# LCDTFT_FPC40P_SPI3_3p2INCH_RTP.net
KiCad netlist of a schematic drawn in Altium Designer
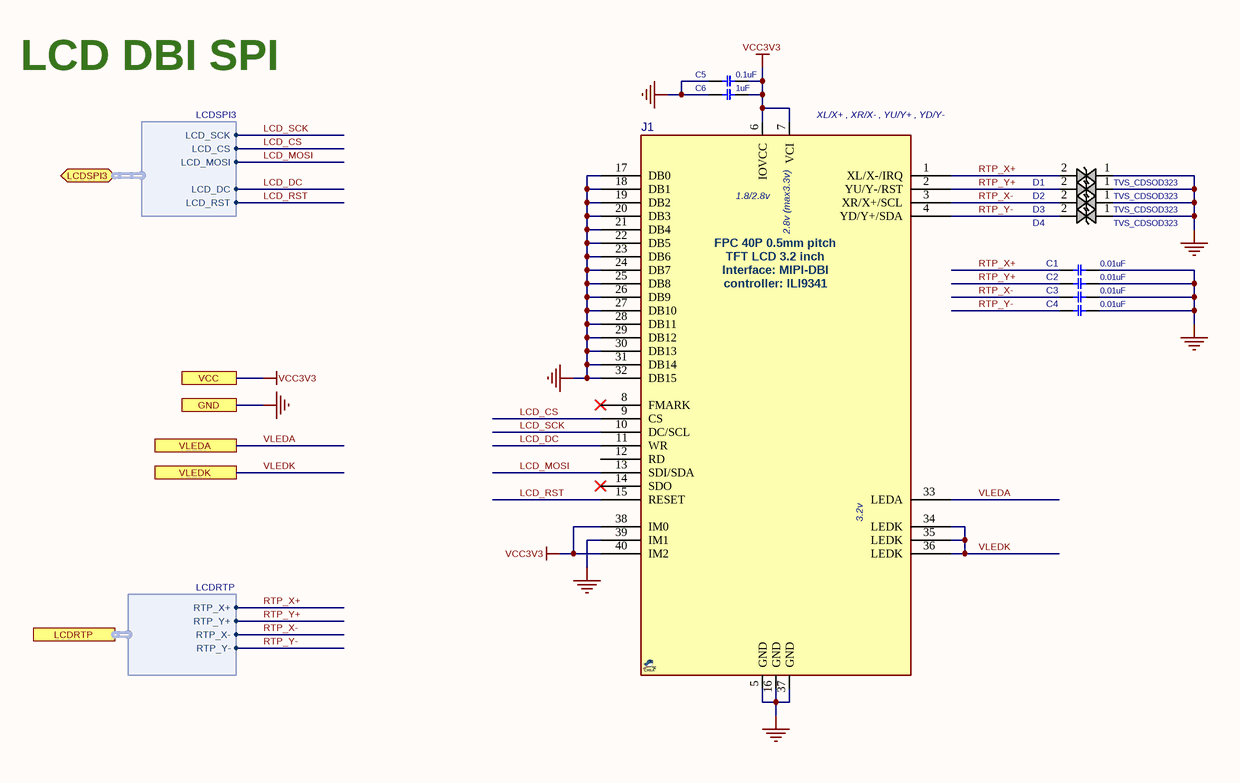
[diagram p0: LCDTFT_FPC40P_SPI3_3p2INCH_RTP.SchDoc]

(export (version "E")
  (design (tool "Eeschema 10.0.6"))
  (components
    (comp (ref "C1")
      (value "0.01uF")
      (footprint "C0402")
      (description "CAP, MLCC")
      (libsource (lib "passive_smd") (part "CAP_SMD_MLCC"))
    )
    (comp (ref "C2")
      (value "0.01uF")
      (footprint "C0402")
      (description "CAP, MLCC")
      (libsource (lib "passive_smd") (part "CAP_SMD_MLCC"))
    )
    (comp (ref "C3")
      (value "0.01uF")
      (footprint "C0402")
      (description "CAP, MLCC")
      (libsource (lib "passive_smd") (part "CAP_SMD_MLCC"))
    )
    (comp (ref "C4")
      (value "0.01uF")
      (footprint "C0402")
      (description "CAP, MLCC")
      (libsource (lib "passive_smd") (part "CAP_SMD_MLCC"))
    )
    (comp (ref "C5")
      (value "0.1uF")
      (footprint "C0402")
      (description "CAP, MLCC")
      (fields (field (name "MANF_P#") "GRM155R71H104KE14D") (field (name "MANF") "Murata"))
      (libsource (lib "passive_smd") (part "CAP_SMD_MLCC"))
    )
    (comp (ref "C6")
      (value "1uF")
      (footprint "C0402")
      (description "CAP, MLCC")
      (libsource (lib "passive_smd") (part "CAP_SMD_MLCC"))
    )
    (comp (ref "D1")
      (value "TVS_CDSOD323")
      (footprint "D0805")
      (description "TVS, ESD PROTECT, Bidirectional")
      (fields (field (name "MANF_P#") "CDSOD323-T12C") (field (name "MANF") "Bourns"))
      (libsource (lib "protect_tvs_esd_fuse") (part "TVS_CDSOD323"))
    )
    (comp (ref "D2")
      (value "TVS_CDSOD323")
      (footprint "D0805")
      (description "TVS, ESD PROTECT, Bidirectional")
      (fields (field (name "MANF_P#") "CDSOD323-T12C") (field (name "MANF") "Bourns"))
      (libsource (lib "protect_tvs_esd_fuse") (part "TVS_CDSOD323"))
    )
    (comp (ref "D3")
      (value "TVS_CDSOD323")
      (footprint "D0805")
      (description "TVS, ESD PROTECT, Bidirectional")
      (fields (field (name "MANF_P#") "CDSOD323-T12C") (field (name "MANF") "Bourns"))
      (libsource (lib "protect_tvs_esd_fuse") (part "TVS_CDSOD323"))
    )
    (comp (ref "D4")
      (value "TVS_CDSOD323")
      (footprint "D0805")
      (description "TVS, ESD PROTECT, Bidirectional")
      (fields (field (name "MANF_P#") "CDSOD323-T12C") (field (name "MANF") "Bourns"))
      (libsource (lib "protect_tvs_esd_fuse") (part "TVS_CDSOD323"))
    )
    (comp (ref "J1")
      (value "FPC50_40")
      (footprint "FPC50_40T")
      (description "LCD TFT Color, FPC40P, 3.2\" with touch")
      (fields (field (name "MANF") "Hirose") (field (name "MANF_P#") "FH12A-40S-0.5SH"))
      (libsource (lib "lcdtft") (part "LCDTFT_DBI_FPC40P_3.2INCH"))
    )
  )
  (nets
    (net (code "3") (name "/LCD_CS") (class "Default")
      (node (ref "J1") (pin "9") (pinfunction "CS_9") (pintype "passive"))
    )
    (net (code "4") (name "/LCD_DC") (class "Default")
      (node (ref "J1") (pin "11") (pinfunction "WR_11") (pintype "passive"))
    )
    (net (code "5") (name "/LCD_MOSI") (class "Default")
      (node (ref "J1") (pin "13") (pinfunction "SDI/SDA_13") (pintype "passive"))
    )
    (net (code "6") (name "/LCD_RST") (class "Default")
      (node (ref "J1") (pin "15") (pinfunction "RESET_15") (pintype "passive"))
    )
    (net (code "7") (name "/LCD_SCK") (class "Default")
      (node (ref "J1") (pin "10") (pinfunction "DC/SCL_10") (pintype "passive"))
    )
    (net (code "8") (name "/RTP_X+") (class "Default")
      (node (ref "C1") (pin "2") (pinfunction "2_2") (pintype "passive"))
      (node (ref "D1") (pin "2") (pinfunction "2_2") (pintype "passive"))
      (node (ref "J1") (pin "1") (pinfunction "XL/X-/IRQ_1") (pintype "passive"))
    )
    (net (code "9") (name "/RTP_X-") (class "Default")
      (node (ref "C3") (pin "2") (pinfunction "2_2") (pintype "passive"))
      (node (ref "D3") (pin "2") (pinfunction "2_2") (pintype "passive"))
      (node (ref "J1") (pin "3") (pinfunction "XR/X+/SCL_3") (pintype "passive"))
    )
    (net (code "10") (name "/RTP_Y+") (class "Default")
      (node (ref "C2") (pin "2") (pinfunction "2_2") (pintype "passive"))
      (node (ref "D2") (pin "2") (pinfunction "2_2") (pintype "passive"))
      (node (ref "J1") (pin "2") (pinfunction "YU/Y-/RST_2") (pintype "passive"))
    )
    (net (code "11") (name "/RTP_Y-") (class "Default")
      (node (ref "C4") (pin "2") (pinfunction "2_2") (pintype "passive"))
      (node (ref "D4") (pin "2") (pinfunction "2_2") (pintype "passive"))
      (node (ref "J1") (pin "4") (pinfunction "YD/Y+/SDA_4") (pintype "passive"))
    )
    (net (code "12") (name "/VLEDA") (class "Default")
      (node (ref "J1") (pin "33") (pinfunction "LEDA_33") (pintype "passive"))
    )
    (net (code "13") (name "/VLEDK") (class "Default")
      (node (ref "J1") (pin "34") (pinfunction "LEDK_34") (pintype "passive"))
      (node (ref "J1") (pin "35") (pinfunction "LEDK_35") (pintype "passive"))
      (node (ref "J1") (pin "36") (pinfunction "LEDK_36") (pintype "passive"))
    )
    (net (code "16") (name "GND") (class "Default")
      (node (ref "C1") (pin "1") (pinfunction "1_1") (pintype "passive"))
      (node (ref "C2") (pin "1") (pinfunction "1_1") (pintype "passive"))
      (node (ref "C3") (pin "1") (pinfunction "1_1") (pintype "passive"))
      (node (ref "C4") (pin "1") (pinfunction "1_1") (pintype "passive"))
      (node (ref "C5") (pin "2") (pinfunction "2_2") (pintype "passive"))
      (node (ref "C6") (pin "2") (pinfunction "2_2") (pintype "passive"))
      (node (ref "D1") (pin "1") (pinfunction "1_1") (pintype "passive"))
      (node (ref "D2") (pin "1") (pinfunction "1_1") (pintype "passive"))
      (node (ref "D3") (pin "1") (pinfunction "1_1") (pintype "passive"))
      (node (ref "D4") (pin "1") (pinfunction "1_1") (pintype "passive"))
      (node (ref "J1") (pin "16") (pinfunction "GND_16") (pintype "passive"))
      (node (ref "J1") (pin "17") (pinfunction "DB0_17") (pintype "passive"))
      (node (ref "J1") (pin "18") (pinfunction "DB1_18") (pintype "passive"))
      (node (ref "J1") (pin "19") (pinfunction "DB2_19") (pintype "passive"))
      (node (ref "J1") (pin "20") (pinfunction "DB3_20") (pintype "passive"))
      (node (ref "J1") (pin "21") (pinfunction "DB4_21") (pintype "passive"))
      (node (ref "J1") (pin "22") (pinfunction "DB5_22") (pintype "passive"))
      (node (ref "J1") (pin "23") (pinfunction "DB6_23") (pintype "passive"))
      (node (ref "J1") (pin "24") (pinfunction "DB7_24") (pintype "passive"))
      (node (ref "J1") (pin "25") (pinfunction "DB8_25") (pintype "passive"))
      (node (ref "J1") (pin "26") (pinfunction "DB9_26") (pintype "passive"))
      (node (ref "J1") (pin "27") (pinfunction "DB10_27") (pintype "passive"))
      (node (ref "J1") (pin "28") (pinfunction "DB11_28") (pintype "passive"))
      (node (ref "J1") (pin "29") (pinfunction "DB12_29") (pintype "passive"))
      (node (ref "J1") (pin "30") (pinfunction "DB13_30") (pintype "passive"))
      (node (ref "J1") (pin "31") (pinfunction "DB14_31") (pintype "passive"))
      (node (ref "J1") (pin "32") (pinfunction "DB15_32") (pintype "passive"))
      (node (ref "J1") (pin "37") (pinfunction "GND_37") (pintype "passive"))
      (node (ref "J1") (pin "39") (pinfunction "IM1_39") (pintype "passive"))
      (node (ref "J1") (pin "5") (pinfunction "GND_5") (pintype "passive"))
    )
    (net (code "17") (name "VCC3V3") (class "Default")
      (node (ref "C5") (pin "1") (pinfunction "1_1") (pintype "passive"))
      (node (ref "C6") (pin "1") (pinfunction "1_1") (pintype "passive"))
      (node (ref "J1") (pin "38") (pinfunction "IM0_38") (pintype "passive"))
      (node (ref "J1") (pin "40") (pinfunction "IM2_40") (pintype "passive"))
      (node (ref "J1") (pin "6") (pinfunction "IOVCC_6") (pintype "passive"))
      (node (ref "J1") (pin "7") (pinfunction "VCI_7") (pintype "passive"))
    )
    (net (code "18") (name "unconnected-(J1-FMARK-Pad8)") (class "Default")
      (node (ref "J1") (pin "8") (pinfunction "FMARK_8") (pintype "passive+no_connect"))
    )
    (net (code "19") (name "unconnected-(J1-RD-Pad12)") (class "Default")
      (node (ref "J1") (pin "12") (pinfunction "RD_12") (pintype "passive"))
    )
    (net (code "20") (name "unconnected-(J1-SDO-Pad14)") (class "Default")
      (node (ref "J1") (pin "14") (pinfunction "SDO_14") (pintype "passive+no_connect"))
    )
  )
)
